# Main.net
KiCad netlist of a schematic drawn in Altium Designer
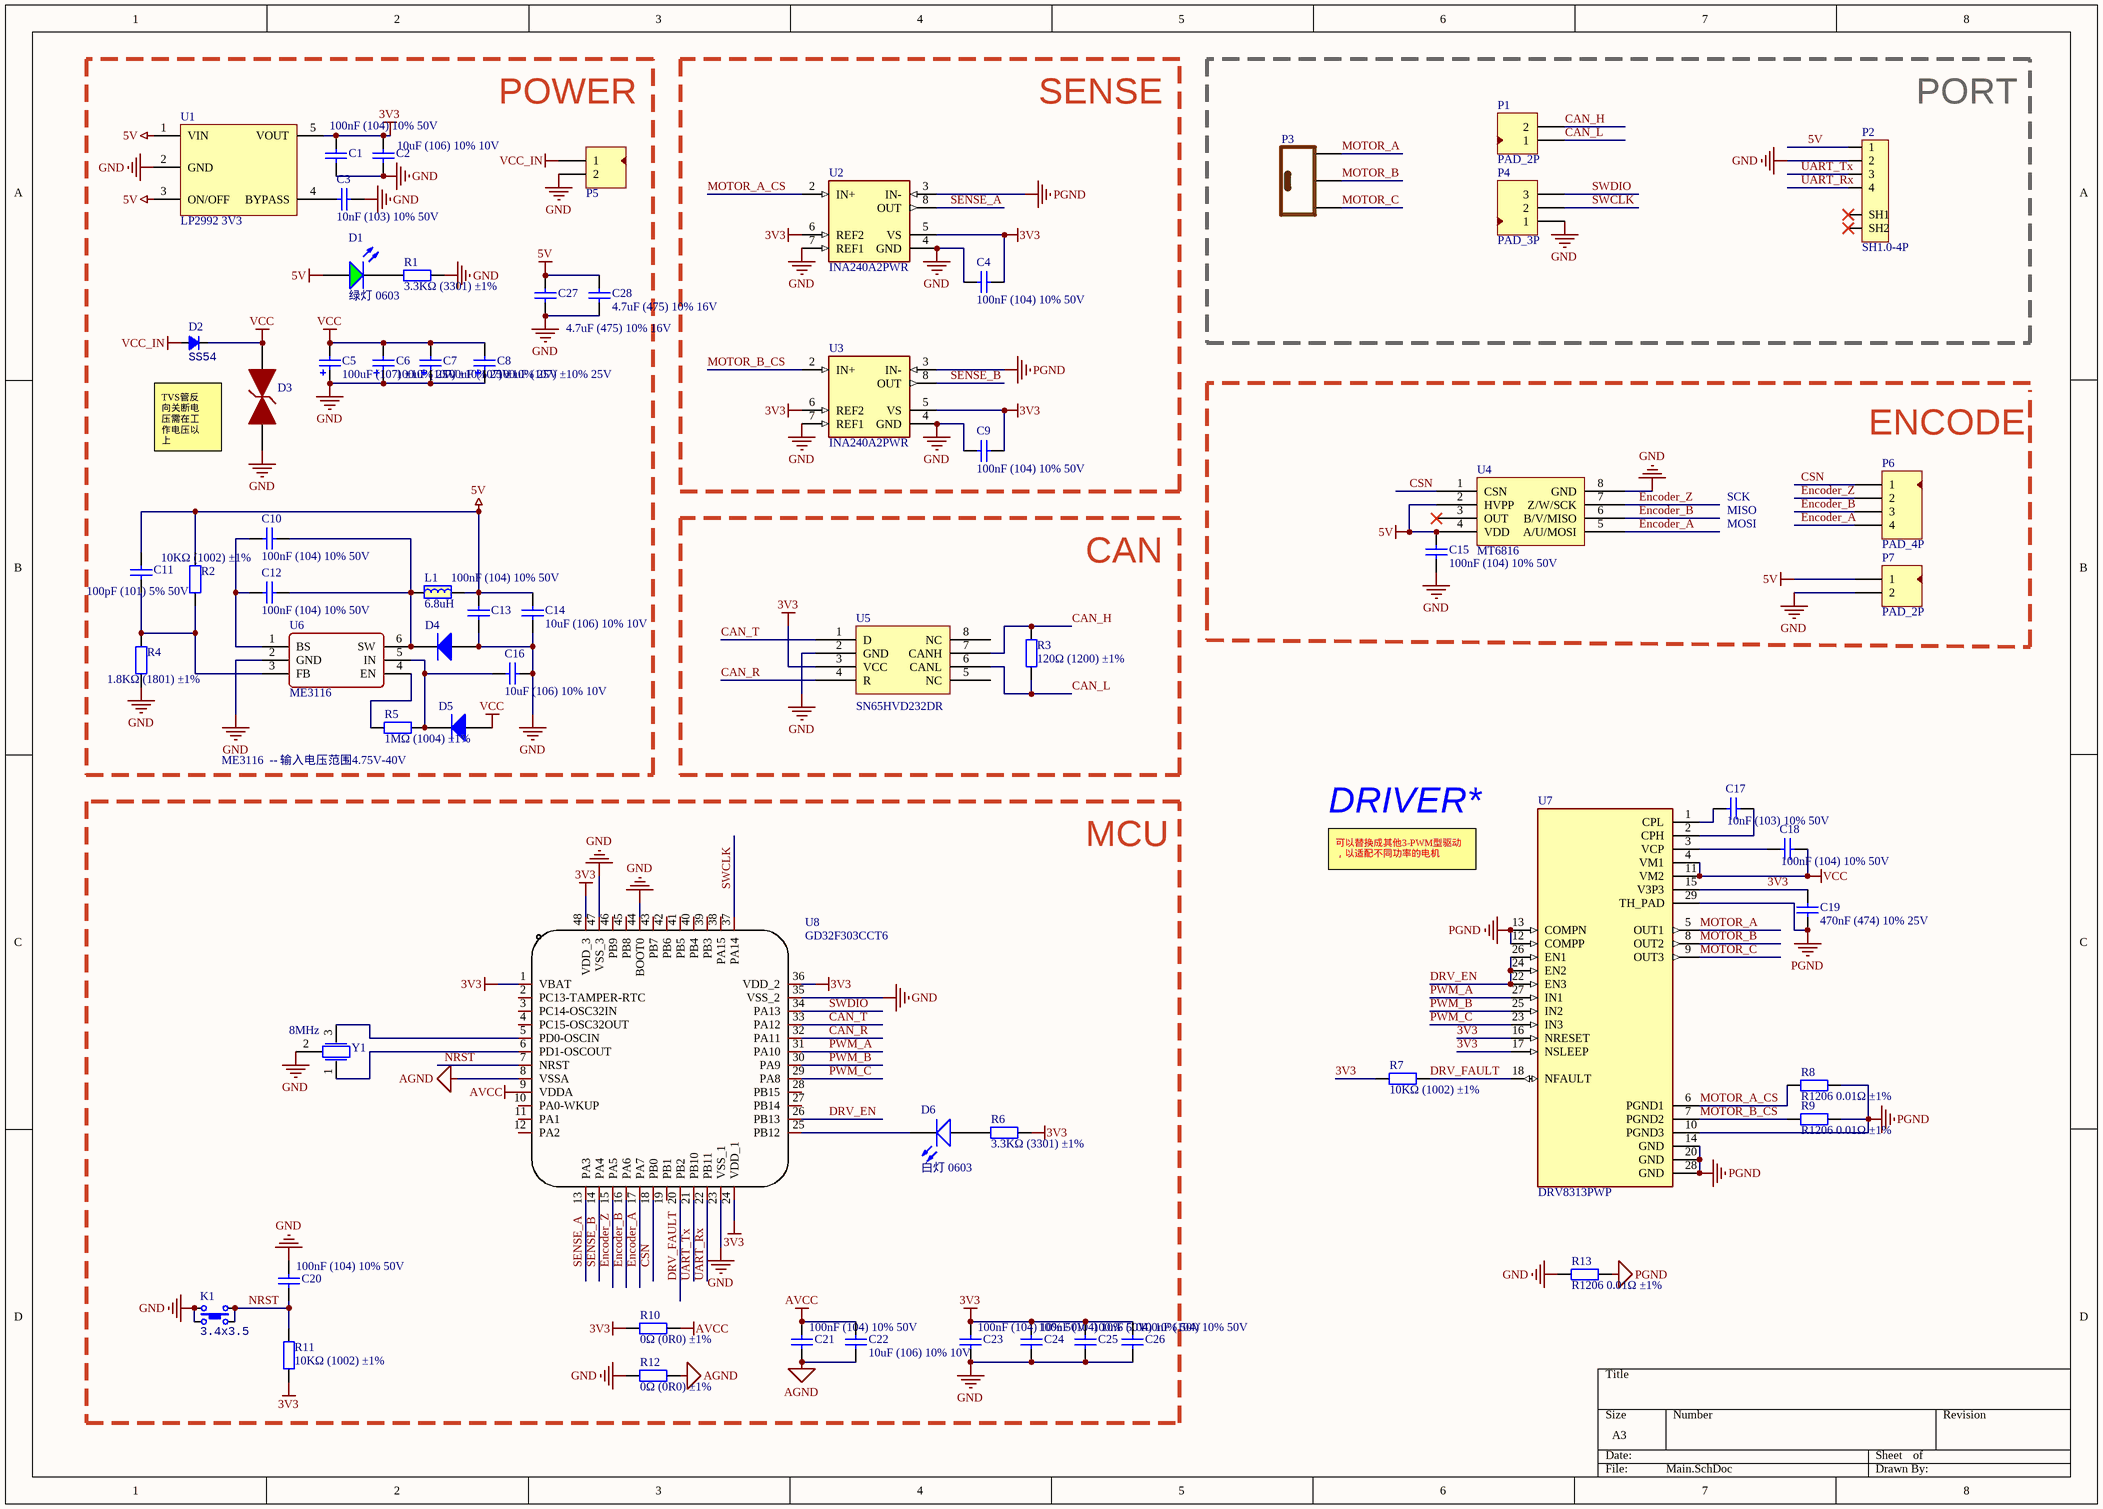
[diagram p0: Main.SchDoc]

(export (version "E")
  (design (tool "Eeschema 10.0.6"))
  (components
    (comp (ref "C1")
      (value "100nF (104) 10% 50V")
      (footprint "0603_C")
      (description "贴片电容")
      (libsource (lib "My_Integrated_Library") (part "0603 100nF (104) 10% 50V"))
    )
    (comp (ref "C2")
      (value "10uF (106) 10% 10V")
      (footprint "0603_C")
      (description "贴片电容")
      (libsource (lib "My_Integrated_Library") (part "0603 10uF (106) 10% 10V"))
    )
    (comp (ref "C3")
      (value "10nF (103) 10% 50V")
      (footprint "0603_C")
      (description "贴片电容")
      (libsource (lib "My_Integrated_Library") (part "0603 10nF (103) 10% 50V"))
    )
    (comp (ref "C4")
      (value "100nF (104) 10% 50V")
      (footprint "0603_C")
      (description "贴片电容")
      (libsource (lib "My_Integrated_Library") (part "0603 100nF (104) 10% 50V"))
    )
    (comp (ref "C5")
      (value "100uF (107) ±10% 25V")
      (footprint "CASE-B_3528")
      (description "钽电容")
      (libsource (lib "My_Integrated_Library") (part "3528 100uF (107) 10% 25V"))
    )
    (comp (ref "C6")
      (value "100uF (107) ±10% 25V")
      (footprint "CASE-B_3528")
      (description "钽电容")
      (libsource (lib "My_Integrated_Library") (part "3528 100uF (107) 10% 25V"))
    )
    (comp (ref "C7")
      (value "100uF (107) ±10% 25V")
      (footprint "CASE-B_3528")
      (description "钽电容")
      (libsource (lib "My_Integrated_Library") (part "3528 100uF (107) 10% 25V"))
    )
    (comp (ref "C8")
      (value "100uF (107) ±10% 25V")
      (footprint "CASE-B_3528")
      (description "钽电容")
      (libsource (lib "My_Integrated_Library") (part "3528 100uF (107) 10% 25V"))
    )
    (comp (ref "C9")
      (value "100nF (104) 10% 50V")
      (footprint "0603_C")
      (description "贴片电容")
      (libsource (lib "My_Integrated_Library") (part "0603 100nF (104) 10% 50V"))
    )
    (comp (ref "C10")
      (value "100nF (104) 10% 50V")
      (footprint "0603_C")
      (description "贴片电容")
      (libsource (lib "My_Integrated_Library") (part "0603 100nF (104) 10% 50V"))
    )
    (comp (ref "C11")
      (value "100pF (101) 5% 50V")
      (footprint "0603_C")
      (description "贴片电容")
      (libsource (lib "My_Integrated_Library") (part "0603 100pF (101) 5% 50V"))
    )
    (comp (ref "C12")
      (value "100nF (104) 10% 50V")
      (footprint "0603_C")
      (description "贴片电容")
      (libsource (lib "My_Integrated_Library") (part "0603 100nF (104) 10% 50V"))
    )
    (comp (ref "C13")
      (value "100nF (104) 10% 50V")
      (footprint "0603_C")
      (description "贴片电容")
      (libsource (lib "My_Integrated_Library") (part "0603 100nF (104) 10% 50V"))
    )
    (comp (ref "C14")
      (value "10uF (106) 10% 10V")
      (footprint "0603_C")
      (description "贴片电容")
      (libsource (lib "My_Integrated_Library") (part "0603 10uF (106) 10% 10V"))
    )
    (comp (ref "C15")
      (value "100nF (104) 10% 50V")
      (footprint "0603_C")
      (description "贴片电容")
      (libsource (lib "My_Integrated_Library") (part "0603 100nF (104) 10% 50V"))
    )
    (comp (ref "C16")
      (value "10uF (106) 10% 10V")
      (footprint "0603_C")
      (description "贴片电容")
      (libsource (lib "My_Integrated_Library") (part "0603 10uF (106) 10% 10V"))
    )
    (comp (ref "C17")
      (value "10nF (103) 10% 50V")
      (footprint "0603_C")
      (description "贴片电容")
      (libsource (lib "My_Integrated_Library") (part "0603 10nF (103) 10% 50V"))
    )
    (comp (ref "C18")
      (value "100nF (104) 10% 50V")
      (footprint "0603_C")
      (description "贴片电容")
      (libsource (lib "My_Integrated_Library") (part "0603 100nF (104) 10% 50V"))
    )
    (comp (ref "C19")
      (value "470nF (474) 10% 25V")
      (footprint "0603_C")
      (description "贴片电容")
      (libsource (lib "My_Integrated_Library") (part "0603 470nF (474) 10% 25V"))
    )
    (comp (ref "C20")
      (value "100nF (104) 10% 50V")
      (footprint "0603_C")
      (description "贴片电容")
      (libsource (lib "My_Integrated_Library") (part "0603 100nF (104) 10% 50V"))
    )
    (comp (ref "C21")
      (value "100nF (104) 10% 50V")
      (footprint "0603_C")
      (description "贴片电容")
      (libsource (lib "My_Integrated_Library") (part "0603 100nF (104) 10% 50V"))
    )
    (comp (ref "C22")
      (value "10uF (106) 10% 10V")
      (footprint "0603_C")
      (description "贴片电容")
      (libsource (lib "My_Integrated_Library") (part "0603 10uF (106) 10% 10V"))
    )
    (comp (ref "C23")
      (value "100nF (104) 10% 50V")
      (footprint "0603_C")
      (description "贴片电容")
      (libsource (lib "My_Integrated_Library") (part "0603 100nF (104) 10% 50V"))
    )
    (comp (ref "C24")
      (value "100nF (104) 10% 50V")
      (footprint "0603_C")
      (description "贴片电容")
      (libsource (lib "My_Integrated_Library") (part "0603 100nF (104) 10% 50V"))
    )
    (comp (ref "C25")
      (value "100nF (104) 10% 50V")
      (footprint "0603_C")
      (description "贴片电容")
      (libsource (lib "My_Integrated_Library") (part "0603 100nF (104) 10% 50V"))
    )
    (comp (ref "C26")
      (value "100nF (104) 10% 50V")
      (footprint "0603_C")
      (description "贴片电容")
      (libsource (lib "My_Integrated_Library") (part "0603 100nF (104) 10% 50V"))
    )
    (comp (ref "C27")
      (value "4.7uF (475) 10% 16V")
      (footprint "0603_C")
      (description "贴片电容")
      (libsource (lib "My_Integrated_Library") (part "0603 4.7uF (475) 10% 16V"))
    )
    (comp (ref "C28")
      (value "4.7uF (475) 10% 16V")
      (footprint "0603_C")
      (description "贴片电容")
      (libsource (lib "My_Integrated_Library") (part "0603 4.7uF (475) 10% 16V"))
    )
    (comp (ref "D1")
      (value "绿灯 0603")
      (footprint "0603_LED_S1")
      (description "发光二极管")
      (libsource (lib "My_Integrated_Library") (part "0603 绿灯"))
    )
    (comp (ref "D2")
      (value "SS54")
      (footprint "DO-214AC")
      (description "Diode")
      (libsource (lib "KitSprout") (part "Diode_SMA"))
    )
    (comp (ref "D3")
      (value "SMBJ28CA")
      (footprint "SMBJ-CA_MFG")
      (libsource (lib "MyPcbLib") (part "SMBJ28CA"))
    )
    (comp (ref "D4")
      (value "二极管-5B5819WS")
      (footprint "SOD-323")
      (description "40V")
      (libsource (lib "MyPcbLib") (part "二极管-5B5817WS"))
    )
    (comp (ref "D5")
      (value "二极管-5B5819WS")
      (footprint "SOD-323")
      (description "40V")
      (libsource (lib "MyPcbLib") (part "二极管-5B5817WS"))
    )
    (comp (ref "D6")
      (value "白灯 0603")
      (footprint "0603_LED_S1")
      (description "发光二极管")
      (libsource (lib "My_Integrated_Library") (part "0603 白灯"))
    )
    (comp (ref "K1")
      (value "3.4x3.5")
      (footprint "ButtonTACT_3.5*3.55_90")
      (description "Button")
      (fields (field (name "Comment") "TACT 4P"))
      (libsource (lib "KitSprout") (part "ButtonTACT"))
    )
    (comp (ref "L1") (value "6.8uH") (footprint "IND-201612") (libsource (lib "MyPcbLib") (part "电感-201612")))
    (comp (ref "P1")
      (value "PAD_2P")
      (footprint "接线焊接点_2P")
      (description "导线焊接点")
      (libsource (lib "") (part "PAD_2P_1"))
    )
    (comp (ref "P2")
      (value "SH1.0-4P")
      (footprint "XP4")
      (libsource (lib "My_Integrated_Library") (part "SH1.0-4P"))
    )
    (comp (ref "P3")
      (value "电机接插件-3P")
      (footprint "AMASS-MR30-M")
      (description "AMASS MR30")
      (libsource (lib "MyPcbLib") (part "电机接插件-3P"))
    )
    (comp (ref "P4")
      (value "PAD_3P")
      (footprint "接线焊接点_3P")
      (description "导线焊接点")
      (libsource (lib "My_Integrated_Library") (part "PAD_3P"))
    )
    (comp (ref "P5")
      (value "Header 2")
      (footprint "HDR1X2")
      (description "接插件")
      (fields (field (name "PUBLISHER") "Altium Limited"))
      (libsource (lib "My_Integrated_Library") (part "Header 2"))
    )
    (comp (ref "P6")
      (value "PAD_4P")
      (footprint "接线焊接点_4P")
      (description "导线焊接点")
      (libsource (lib "My_Integrated_Library") (part "PAD_4P"))
    )
    (comp (ref "P7")
      (value "PAD_2P")
      (footprint "接线焊接点_2P")
      (description "导线焊接点")
      (libsource (lib "My_Integrated_Library") (part "PAD_2P"))
    )
    (comp (ref "R1")
      (value "3.3KΩ (3301) ±1%")
      (footprint "0603_R")
      (description "贴片电阻")
      (libsource (lib "My_Integrated_Library") (part "0603 3.3KΩ (3301) 1%"))
    )
    (comp (ref "R2")
      (value "10KΩ (1002) ±1%")
      (footprint "0603_R")
      (description "贴片电阻")
      (libsource (lib "") (part "0603 10KΩ (1002) 1%_1"))
    )
    (comp (ref "R3")
      (value "120Ω (1200) ±1%")
      (footprint "0603_R")
      (description "贴片电阻")
      (libsource (lib "My_Integrated_Library") (part "0603 120Ω (1200) 1%"))
    )
    (comp (ref "R4")
      (value "1.8KΩ (1801) ±1%")
      (footprint "0603_R")
      (description "贴片电阻")
      (libsource (lib "My_Integrated_Library") (part "0603 1.8KΩ (1801) 1%"))
    )
    (comp (ref "R5")
      (value "1MΩ (1004) ±1%")
      (footprint "0603_R")
      (description "贴片电阻")
      (libsource (lib "My_Integrated_Library") (part "0603 1MΩ (1004) 1%"))
    )
    (comp (ref "R6")
      (value "3.3KΩ (3301) ±1%")
      (footprint "0603_R")
      (description "贴片电阻")
      (libsource (lib "My_Integrated_Library") (part "0603 3.3KΩ (3301) 1%"))
    )
    (comp (ref "R7")
      (value "10KΩ (1002) ±1%")
      (footprint "0603_R")
      (description "贴片电阻")
      (libsource (lib "My_Integrated_Library") (part "0603 10KΩ (1002) 1%"))
    )
    (comp (ref "R8")
      (value "R1206 0.01Ω ±1%")
      (footprint "1206_R")
      (description "电流检测电阻")
      (libsource (lib "My_Integrated_Library") (part "1206 0.005Ω 1%"))
    )
    (comp (ref "R9")
      (value "R1206 0.01Ω ±1%")
      (footprint "1206_R")
      (description "电流检测电阻")
      (libsource (lib "My_Integrated_Library") (part "1206 0.005Ω 1%"))
    )
    (comp (ref "R10")
      (value "0Ω (0R0) ±1%")
      (footprint "0603_R")
      (description "贴片电阻")
      (libsource (lib "My_Integrated_Library") (part "0603 0Ω (0R0) 1%"))
    )
    (comp (ref "R11")
      (value "10KΩ (1002) ±1%")
      (footprint "0603_R")
      (description "贴片电阻")
      (libsource (lib "") (part "0603 10KΩ (1002) 1%_1"))
    )
    (comp (ref "R12")
      (value "0Ω (0R0) ±1%")
      (footprint "0603_R")
      (description "贴片电阻")
      (libsource (lib "My_Integrated_Library") (part "0603 0Ω (0R0) 1%"))
    )
    (comp (ref "R13")
      (value "R1206 0.01Ω ±1%")
      (footprint "1206_R")
      (description "电流检测电阻")
      (libsource (lib "My_Integrated_Library") (part "1206 0.005Ω 1%"))
    )
    (comp (ref "U1")
      (value "LP2992 3V3")
      (footprint "SOT23-5")
      (description "LDO")
      (libsource (lib "MyPcbLib") (part "LP2992"))
    )
    (comp (ref "U2")
      (value "INA240A2PWR")
      (footprint "SOP65 P640X120-8N")
      (fields (field (name "MF") "Texas Instruments"))
      (libsource (lib "mLib") (part "INA240A2PWR"))
    )
    (comp (ref "U3")
      (value "INA240A2PWR")
      (footprint "SOP65 P640X120-8N")
      (fields (field (name "MF") "Texas Instruments"))
      (libsource (lib "mLib") (part "INA240A2PWR"))
    )
    (comp (ref "U4")
      (value "MT6816")
      (footprint "SOP8-PP-AT8870")
      (libsource (lib "My_Integrated_Library") (part "MT6816"))
    )
    (comp (ref "U5")
      (value "SN65HVD232D")
      (footprint "SO-8")
      (fields
        (field (name "MANUFACTURER") "Texas Instruments")
        (field (name "MANUFACTURER PART NUMBER") "SN65HVD232DR")
      )
      (libsource (lib "MyPcbLib") (part "SN65HVD232D"))
    )
    (comp (ref "U6")
      (value "ME3116")
      (footprint "SOT23-6")
      (description "DC-DC")
      (libsource (lib "MyPcbLib") (part "ME3116"))
    )
    (comp (ref "U7")
      (value "DRV8313PWP")
      (footprint "HTSSOP-28")
      (description "65-V max, 3-A peak 3-phase motor driver 28-HTSSOP -40 to 125")
      (fields (field (name "MF") "Texas Instruments"))
      (libsource (lib "MyPcbLib") (part "DRV8313PWP"))
    )
    (comp (ref "U8")
      (value "GD32F303CCT6")
      (footprint "LQFP_48")
      (libsource (lib "MCU") (part "GD32F303CCT6"))
    )
    (comp (ref "Y1")
      (value "8MHz")
      (footprint "晶振-3P")
      (description "村田贴片")
      (libsource (lib "MyPcbLib") (part "晶振-3Pin"))
    )
  )
  (nets
    (net (code "1") (name "/CAN_H") (class "Default")
      (node (ref "P1") (pin "2") (pinfunction "2_2") (pintype "passive"))
      (node (ref "R3") (pin "2") (pinfunction "2_2") (pintype "passive"))
      (node (ref "U5") (pin "7") (pinfunction "CANH_7") (pintype "passive"))
    )
    (net (code "2") (name "/CAN_L") (class "Default")
      (node (ref "P1") (pin "1") (pinfunction "1_1") (pintype "passive"))
      (node (ref "R3") (pin "1") (pinfunction "1_1") (pintype "passive"))
      (node (ref "U5") (pin "6") (pinfunction "CANL_6") (pintype "passive"))
    )
    (net (code "3") (name "/CAN_R") (class "Default")
      (node (ref "U5") (pin "4") (pinfunction "R_4") (pintype "passive"))
      (node (ref "U8") (pin "32") (pinfunction "PA11_32") (pintype "passive"))
    )
    (net (code "4") (name "/CAN_T") (class "Default")
      (node (ref "U5") (pin "1") (pinfunction "D_1") (pintype "passive"))
      (node (ref "U8") (pin "33") (pinfunction "PA12_33") (pintype "passive"))
    )
    (net (code "5") (name "/CSN") (class "Default")
      (node (ref "P6") (pin "1") (pinfunction "1_1") (pintype "passive"))
      (node (ref "U4") (pin "1") (pinfunction "CSN_1") (pintype "passive"))
      (node (ref "U8") (pin "18") (pinfunction "PB0_18") (pintype "passive"))
    )
    (net (code "6") (name "/DRV_EN") (class "Default")
      (node (ref "U7") (pin "22") (pinfunction "EN3_22") (pintype "input"))
      (node (ref "U7") (pin "24") (pinfunction "EN2_24") (pintype "input"))
      (node (ref "U7") (pin "26") (pinfunction "EN1_26") (pintype "input"))
      (node (ref "U8") (pin "26") (pinfunction "PB13_26") (pintype "passive"))
    )
    (net (code "7") (name "/DRV_FAULT") (class "Default")
      (node (ref "R7") (pin "2") (pinfunction "2_2") (pintype "passive"))
      (node (ref "U7") (pin "18") (pinfunction "NFAULT_18") (pintype "bidirectional"))
      (node (ref "U8") (pin "20") (pinfunction "PB2_20") (pintype "passive"))
    )
    (net (code "8") (name "/Encoder_A") (class "Default")
      (node (ref "P6") (pin "4") (pinfunction "4_4") (pintype "passive"))
      (node (ref "U4") (pin "5") (pinfunction "A/U/MOSI_5") (pintype "passive"))
      (node (ref "U8") (pin "17") (pinfunction "PA7_17") (pintype "passive"))
    )
    (net (code "9") (name "/Encoder_B") (class "Default")
      (node (ref "P6") (pin "3") (pinfunction "3_3") (pintype "passive"))
      (node (ref "U4") (pin "6") (pinfunction "B/V/MISO_6") (pintype "passive"))
      (node (ref "U8") (pin "16") (pinfunction "PA6_16") (pintype "passive"))
    )
    (net (code "10") (name "/Encoder_Z") (class "Default")
      (node (ref "P6") (pin "2") (pinfunction "2_2") (pintype "passive"))
      (node (ref "U4") (pin "7") (pinfunction "Z/W/SCK_7") (pintype "passive"))
      (node (ref "U8") (pin "15") (pinfunction "PA5_15") (pintype "passive"))
    )
    (net (code "11") (name "/MOTOR_A") (class "Default")
      (node (ref "P3") (pin "3") (pinfunction "3_3") (pintype "passive"))
      (node (ref "U7") (pin "5") (pinfunction "OUT1_5") (pintype "output"))
    )
    (net (code "12") (name "/MOTOR_A_CS") (class "Default")
      (node (ref "R8") (pin "1") (pinfunction "1_1") (pintype "passive"))
      (node (ref "U2") (pin "2") (pinfunction "IN+_2") (pintype "input"))
      (node (ref "U7") (pin "6") (pinfunction "PGND1_6") (pintype "power_in"))
    )
    (net (code "13") (name "/MOTOR_B") (class "Default")
      (node (ref "P3") (pin "2") (pinfunction "2_2") (pintype "passive"))
      (node (ref "U7") (pin "8") (pinfunction "OUT2_8") (pintype "output"))
    )
    (net (code "14") (name "/MOTOR_B_CS") (class "Default")
      (node (ref "R9") (pin "1") (pinfunction "1_1") (pintype "passive"))
      (node (ref "U3") (pin "2") (pinfunction "IN+_2") (pintype "input"))
      (node (ref "U7") (pin "7") (pinfunction "PGND2_7") (pintype "power_in"))
    )
    (net (code "15") (name "/MOTOR_C") (class "Default")
      (node (ref "P3") (pin "1") (pinfunction "1_1") (pintype "passive"))
      (node (ref "U7") (pin "9") (pinfunction "OUT3_9") (pintype "output"))
    )
    (net (code "16") (name "/NRST") (class "Default")
      (node (ref "C20") (pin "1") (pinfunction "1_1") (pintype "passive"))
      (node (ref "K1") (pin "1") (pinfunction "1_1") (pintype "passive"))
      (node (ref "K1") (pin "3") (pinfunction "3_3") (pintype "passive"))
      (node (ref "R11") (pin "2") (pinfunction "2_2") (pintype "passive"))
      (node (ref "U8") (pin "7") (pinfunction "NRST_7") (pintype "passive"))
    )
    (net (code "17") (name "/PWM_A") (class "Default")
      (node (ref "U7") (pin "27") (pinfunction "IN1_27") (pintype "input"))
      (node (ref "U8") (pin "31") (pinfunction "PA10_31") (pintype "passive"))
    )
    (net (code "18") (name "/PWM_B") (class "Default")
      (node (ref "U7") (pin "25") (pinfunction "IN2_25") (pintype "input"))
      (node (ref "U8") (pin "30") (pinfunction "PA9_30") (pintype "passive"))
    )
    (net (code "19") (name "/PWM_C") (class "Default")
      (node (ref "U7") (pin "23") (pinfunction "IN3_23") (pintype "input"))
      (node (ref "U8") (pin "29") (pinfunction "PA8_29") (pintype "passive"))
    )
    (net (code "20") (name "/SENSE_A") (class "Default")
      (node (ref "U2") (pin "8") (pinfunction "OUT_8") (pintype "output"))
      (node (ref "U8") (pin "13") (pinfunction "PA3_13") (pintype "passive"))
    )
    (net (code "21") (name "/SENSE_B") (class "Default")
      (node (ref "U3") (pin "8") (pinfunction "OUT_8") (pintype "output"))
      (node (ref "U8") (pin "14") (pinfunction "PA4_14") (pintype "passive"))
    )
    (net (code "22") (name "/SWCLK") (class "Default")
      (node (ref "P4") (pin "2") (pinfunction "2_2") (pintype "passive"))
      (node (ref "U8") (pin "37") (pinfunction "PA14_37") (pintype "passive"))
    )
    (net (code "23") (name "/SWDIO") (class "Default")
      (node (ref "P4") (pin "3") (pinfunction "3_3") (pintype "passive"))
      (node (ref "U8") (pin "34") (pinfunction "PA13_34") (pintype "passive"))
    )
    (net (code "24") (name "/UART_Rx") (class "Default")
      (node (ref "P2") (pin "4") (pinfunction "4_4") (pintype "passive"))
      (node (ref "U8") (pin "22") (pinfunction "PB11_22") (pintype "passive"))
    )
    (net (code "25") (name "/UART_Tx") (class "Default")
      (node (ref "P2") (pin "3") (pinfunction "3_3") (pintype "passive"))
      (node (ref "U8") (pin "21") (pinfunction "PB10_21") (pintype "passive"))
    )
    (net (code "26") (name "3V3") (class "Default")
      (node (ref "C1") (pin "2") (pinfunction "2_2") (pintype "passive"))
      (node (ref "C19") (pin "2") (pinfunction "2_2") (pintype "passive"))
      (node (ref "C2") (pin "2") (pinfunction "2_2") (pintype "passive"))
      (node (ref "C23") (pin "2") (pinfunction "2_2") (pintype "passive"))
      (node (ref "C24") (pin "2") (pinfunction "2_2") (pintype "passive"))
      (node (ref "C25") (pin "2") (pinfunction "2_2") (pintype "passive"))
      (node (ref "C26") (pin "2") (pinfunction "2_2") (pintype "passive"))
      (node (ref "C4") (pin "2") (pinfunction "2_2") (pintype "passive"))
      (node (ref "C9") (pin "1") (pinfunction "1_1") (pintype "passive"))
      (node (ref "R10") (pin "1") (pinfunction "1_1") (pintype "passive"))
      (node (ref "R11") (pin "1") (pinfunction "1_1") (pintype "passive"))
      (node (ref "R6") (pin "2") (pinfunction "2_2") (pintype "passive"))
      (node (ref "R7") (pin "1") (pinfunction "1_1") (pintype "passive"))
      (node (ref "U1") (pin "5") (pinfunction "VOUT_5") (pintype "passive"))
      (node (ref "U2") (pin "5") (pinfunction "VS_5") (pintype "power_in"))
      (node (ref "U2") (pin "6") (pinfunction "REF2_6") (pintype "input"))
      (node (ref "U3") (pin "5") (pinfunction "VS_5") (pintype "power_in"))
      (node (ref "U3") (pin "6") (pinfunction "REF2_6") (pintype "input"))
      (node (ref "U5") (pin "3") (pinfunction "VCC_3") (pintype "passive"))
      (node (ref "U7") (pin "15") (pinfunction "V3P3_15") (pintype "power_in"))
      (node (ref "U7") (pin "16") (pinfunction "NRESET_16") (pintype "input"))
      (node (ref "U7") (pin "17") (pinfunction "NSLEEP_17") (pintype "input"))
      (node (ref "U8") (pin "1") (pinfunction "VBAT_1") (pintype "passive"))
      (node (ref "U8") (pin "24") (pinfunction "VDD_1_24") (pintype "passive"))
      (node (ref "U8") (pin "36") (pinfunction "VDD_2_36") (pintype "passive"))
      (node (ref "U8") (pin "48") (pinfunction "VDD_3_48") (pintype "passive"))
    )
    (net (code "27") (name "5V") (class "Default")
      (node (ref "C11") (pin "2") (pinfunction "2_2") (pintype "passive"))
      (node (ref "C13") (pin "2") (pinfunction "2_2") (pintype "passive"))
      (node (ref "C14") (pin "2") (pinfunction "2_2") (pintype "passive"))
      (node (ref "C15") (pin "2") (pinfunction "2_2") (pintype "passive"))
      (node (ref "C27") (pin "2") (pinfunction "2_2") (pintype "passive"))
      (node (ref "C28") (pin "2") (pinfunction "2_2") (pintype "passive"))
      (node (ref "D1") (pin "A") (pinfunction "A_A") (pintype "passive"))
      (node (ref "L1") (pin "2") (pinfunction "2_2") (pintype "passive"))
      (node (ref "P2") (pin "1") (pinfunction "1_1") (pintype "passive"))
      (node (ref "P7") (pin "1") (pinfunction "1_1") (pintype "passive"))
      (node (ref "R2") (pin "2") (pinfunction "2_2") (pintype "passive"))
      (node (ref "U1") (pin "1") (pinfunction "VIN_1") (pintype "passive"))
      (node (ref "U1") (pin "3") (pinfunction "ON/OFF_3") (pintype "passive"))
      (node (ref "U4") (pin "2") (pinfunction "HVPP_2") (pintype "passive"))
      (node (ref "U4") (pin "4") (pinfunction "VDD_4") (pintype "passive"))
    )
    (net (code "28") (name "AGND") (class "Default")
      (node (ref "C21") (pin "1") (pinfunction "1_1") (pintype "passive"))
      (node (ref "C22") (pin "1") (pinfunction "1_1") (pintype "passive"))
      (node (ref "R12") (pin "2") (pinfunction "2_2") (pintype "passive"))
      (node (ref "U8") (pin "8") (pinfunction "VSSA_8") (pintype "passive"))
    )
    (net (code "29") (name "AVCC") (class "Default")
      (node (ref "C21") (pin "2") (pinfunction "2_2") (pintype "passive"))
      (node (ref "C22") (pin "2") (pinfunction "2_2") (pintype "passive"))
      (node (ref "R10") (pin "2") (pinfunction "2_2") (pintype "passive"))
      (node (ref "U8") (pin "9") (pinfunction "VDDA_9") (pintype "passive"))
    )
    (net (code "30") (name "GND") (class "Default")
      (node (ref "C1") (pin "1") (pinfunction "1_1") (pintype "passive"))
      (node (ref "C13") (pin "1") (pinfunction "1_1") (pintype "passive"))
      (node (ref "C14") (pin "1") (pinfunction "1_1") (pintype "passive"))
      (node (ref "C15") (pin "1") (pinfunction "1_1") (pintype "passive"))
      (node (ref "C16") (pin "1") (pinfunction "1_1") (pintype "passive"))
      (node (ref "C2") (pin "1") (pinfunction "1_1") (pintype "passive"))
      (node (ref "C20") (pin "2") (pinfunction "2_2") (pintype "passive"))
      (node (ref "C23") (pin "1") (pinfunction "1_1") (pintype "passive"))
      (node (ref "C24") (pin "1") (pinfunction "1_1") (pintype "passive"))
      (node (ref "C25") (pin "1") (pinfunction "1_1") (pintype "passive"))
      (node (ref "C26") (pin "1") (pinfunction "1_1") (pintype "passive"))
      (node (ref "C27") (pin "1") (pinfunction "1_1") (pintype "passive"))
      (node (ref "C28") (pin "1") (pinfunction "1_1") (pintype "passive"))
      (node (ref "C3") (pin "2") (pinfunction "2_2") (pintype "passive"))
      (node (ref "C4") (pin "1") (pinfunction "1_1") (pintype "passive"))
      (node (ref "C5") (pin "1") (pinfunction "1_1") (pintype "passive"))
      (node (ref "C6") (pin "1") (pinfunction "1_1") (pintype "passive"))
      (node (ref "C7") (pin "1") (pinfunction "1_1") (pintype "passive"))
      (node (ref "C8") (pin "1") (pinfunction "1_1") (pintype "passive"))
      (node (ref "C9") (pin "2") (pinfunction "2_2") (pintype "passive"))
      (node (ref "D3") (pin "1") (pinfunction "1_1") (pintype "passive"))
      (node (ref "D4") (pin "1") (pinfunction "A_1") (pintype "passive"))
      (node (ref "K1") (pin "2") (pinfunction "2_2") (pintype "passive"))
      (node (ref "K1") (pin "4") (pinfunction "4_4") (pintype "passive"))
      (node (ref "P2") (pin "2") (pinfunction "2_2") (pintype "passive"))
      (node (ref "P4") (pin "1") (pinfunction "1_1") (pintype "passive"))
      (node (ref "P5") (pin "2") (pinfunction "2_2") (pintype "passive"))
      (node (ref "P7") (pin "2") (pinfunction "2_2") (pintype "passive"))
      (node (ref "R1") (pin "2") (pinfunction "2_2") (pintype "passive"))
      (node (ref "R12") (pin "1") (pinfunction "1_1") (pintype "passive"))
      (node (ref "R13") (pin "1") (pinfunction "1_1") (pintype "passive"))
      (node (ref "R4") (pin "1") (pinfunction "1_1") (pintype "passive"))
      (node (ref "U1") (pin "2") (pinfunction "GND_2") (pintype "passive"))
      (node (ref "U2") (pin "4") (pinfunction "GND_4") (pintype "power_in"))
      (node (ref "U2") (pin "7") (pinfunction "REF1_7") (pintype "input"))
      (node (ref "U3") (pin "4") (pinfunction "GND_4") (pintype "power_in"))
      (node (ref "U3") (pin "7") (pinfunction "REF1_7") (pintype "input"))
      (node (ref "U4") (pin "8") (pinfunction "GND_8") (pintype "passive"))
      (node (ref "U5") (pin "2") (pinfunction "GND_2") (pintype "passive"))
      (node (ref "U6") (pin "2") (pinfunction "GND_2") (pintype "passive"))
      (node (ref "U8") (pin "23") (pinfunction "VSS_1_23") (pintype "passive"))
      (node (ref "U8") (pin "35") (pinfunction "VSS_2_35") (pintype "passive"))
      (node (ref "U8") (pin "44") (pinfunction "BOOT0_44") (pintype "passive"))
      (node (ref "U8") (pin "47") (pinfunction "VSS_3_47") (pintype "passive"))
      (node (ref "Y1") (pin "2") (pinfunction "2_2") (pintype "passive"))
    )
    (net (code "31") (name "Net-(D1-PadK)") (class "Default")
      (node (ref "D1") (pin "K") (pinfunction "K_K") (pintype "passive"))
      (node (ref "R1") (pin "1") (pinfunction "1_1") (pintype "passive"))
    )
    (net (code "32") (name "Net-(D4-K)") (class "Default")
      (node (ref "C10") (pin "1") (pinfunction "1_1") (pintype "passive"))
      (node (ref "C12") (pin "1") (pinfunction "1_1") (pintype "passive"))
      (node (ref "D4") (pin "2") (pinfunction "K_2") (pintype "passive"))
      (node (ref "L1") (pin "1") (pintype "passive"))
      (node (ref "U6") (pin "6") (pinfunction "SW_6") (pintype "passive"))
    )
    (net (code "33") (name "Net-(D5-K)") (class "Default")
      (node (ref "C16") (pin "2") (pinfunction "2_2") (pintype "passive"))
      (node (ref "D5") (pin "2") (pinfunction "K_2") (pintype "passive"))
      (node (ref "R5") (pin "2") (pinfunction "2_2") (pintype "passive"))
      (node (ref "U6") (pin "5") (pinfunction "IN_5") (pintype "passive"))
    )
    (net (code "34") (name "Net-(D6-PadA)") (class "Default")
      (node (ref "D6") (pin "A") (pinfunction "A_A") (pintype "passive"))
      (node (ref "R6") (pin "1") (pinfunction "1_1") (pintype "passive"))
    )
    (net (code "35") (name "Net-(U1-BYPASS)") (class "Default")
      (node (ref "C3") (pin "1") (pinfunction "1_1") (pintype "passive"))
      (node (ref "U1") (pin "4") (pinfunction "BYPASS_4") (pintype "passive"))
    )
    (net (code "36") (name "Net-(U6-BS)") (class "Default")
      (node (ref "C10") (pin "2") (pinfunction "2_2") (pintype "passive"))
      (node (ref "C12") (pin "2") (pinfunction "2_2") (pintype "passive"))
      (node (ref "U6") (pin "1") (pinfunction "BS_1") (pintype "passive"))
    )
    (net (code "37") (name "Net-(U6-EN)") (class "Default")
      (node (ref "R5") (pin "1") (pinfunction "1_1") (pintype "passive"))
      (node (ref "U6") (pin "4") (pinfunction "EN_4") (pintype "passive"))
    )
    (net (code "38") (name "Net-(U6-FB)") (class "Default")
      (node (ref "C11") (pin "1") (pinfunction "1_1") (pintype "passive"))
      (node (ref "R2") (pin "1") (pinfunction "1_1") (pintype "passive"))
      (node (ref "R4") (pin "2") (pinfunction "2_2") (pintype "passive"))
      (node (ref "U6") (pin "3") (pinfunction "FB_3") (pintype "passive"))
    )
    (net (code "39") (name "Net-(U7-CPH)") (class "Default")
      (node (ref "C17") (pin "2") (pinfunction "2_2") (pintype "passive"))
      (node (ref "U7") (pin "2") (pinfunction "CPH_2") (pintype "power_in"))
    )
    (net (code "40") (name "Net-(U7-CPL)") (class "Default")
      (node (ref "C17") (pin "1") (pinfunction "1_1") (pintype "passive"))
      (node (ref "U7") (pin "1") (pinfunction "CPL_1") (pintype "power_in"))
    )
    (net (code "41") (name "Net-(U7-VCP)") (class "Default")
      (node (ref "C18") (pin "2") (pinfunction "2_2") (pintype "passive"))
      (node (ref "U7") (pin "3") (pinfunction "VCP_3") (pintype "power_in"))
    )
    (net (code "42") (name "Net-(U8-PB12)") (class "Default")
      (node (ref "D6") (pin "K") (pinfunction "K_K") (pintype "passive"))
      (node (ref "U8") (pin "25") (pinfunction "PB12_25") (pintype "passive"))
    )
    (net (code "43") (name "Net-(U8-PD0-OSCIN)") (class "Default")
      (node (ref "U8") (pin "5") (pinfunction "PD0-OSCIN_5") (pintype "passive"))
      (node (ref "Y1") (pin "3") (pinfunction "3_3") (pintype "passive"))
    )
    (net (code "44") (name "Net-(U8-PD1-OSCOUT)") (class "Default")
      (node (ref "U8") (pin "6") (pinfunction "PD1-OSCOUT_6") (pintype "passive"))
      (node (ref "Y1") (pin "1") (pinfunction "1_1") (pintype "passive"))
    )
    (net (code "45") (name "PGND") (class "Default")
      (node (ref "C19") (pin "1") (pinfunction "1_1") (pintype "passive"))
      (node (ref "R13") (pin "2") (pinfunction "2_2") (pintype "passive"))
      (node (ref "R8") (pin "2") (pinfunction "2_2") (pintype "passive"))
      (node (ref "R9") (pin "2") (pinfunction "2_2") (pintype "passive"))
      (node (ref "U2") (pin "3") (pinfunction "IN-_3") (pintype "input"))
      (node (ref "U3") (pin "3") (pinfunction "IN-_3") (pintype "input"))
      (node (ref "U7") (pin "10") (pinfunction "PGND3_10") (pintype "power_in"))
      (node (ref "U7") (pin "12") (pinfunction "COMPP_12") (pintype "input"))
      (node (ref "U7") (pin "13") (pinfunction "COMPN_13") (pintype "input"))
      (node (ref "U7") (pin "14") (pinfunction "GND_14") (pintype "power_in"))
      (node (ref "U7") (pin "20") (pinfunction "GND_20") (pintype "power_in"))
      (node (ref "U7") (pin "28") (pinfunction "GND_28") (pintype "power_in"))
      (node (ref "U7") (pin "29") (pinfunction "TH_PAD_29") (pintype "power_in"))
    )
    (net (code "46") (name "VCC") (class "Default")
      (node (ref "C18") (pin "1") (pinfunction "1_1") (pintype "passive"))
      (node (ref "C5") (pin "2") (pinfunction "2_2") (pintype "passive"))
      (node (ref "C6") (pin "2") (pinfunction "2_2") (pintype "passive"))
      (node (ref "C7") (pin "2") (pinfunction "2_2") (pintype "passive"))
      (node (ref "C8") (pin "2") (pinfunction "2_2") (pintype "passive"))
      (node (ref "D2") (pin "2") (pinfunction "K_2") (pintype "passive"))
      (node (ref "D3") (pin "2") (pinfunction "2_2") (pintype "passive"))
      (node (ref "D5") (pin "1") (pinfunction "A_1") (pintype "passive"))
      (node (ref "U7") (pin "11") (pinfunction "VM2_11") (pintype "power_in"))
      (node (ref "U7") (pin "4") (pinfunction "VM1_4") (pintype "power_in"))
    )
    (net (code "47") (name "VCC_IN") (class "Default")
      (node (ref "D2") (pin "1") (pinfunction "A_1") (pintype "passive"))
      (node (ref "P5") (pin "1") (pinfunction "1_1") (pintype "passive"))
    )
    (net (code "48") (name "unconnected-(P2-PadSH1)") (class "Default")
      (node (ref "P2") (pin "SH1") (pinfunction "SH1_SH1") (pintype "passive+no_connect"))
    )
    (net (code "49") (name "unconnected-(P2-PadSH2)") (class "Default")
      (node (ref "P2") (pin "SH2") (pinfunction "SH2_SH2") (pintype "passive+no_connect"))
    )
    (net (code "50") (name "unconnected-(U4-OUT-Pad3)") (class "Default")
      (node (ref "U4") (pin "3") (pinfunction "OUT_3") (pintype "passive+no_connect"))
    )
    (net (code "51") (name "unconnected-(U5-NC-Pad5)") (class "Default")
      (node (ref "U5") (pin "5") (pinfunction "NC_5") (pintype "passive"))
    )
    (net (code "52") (name "unconnected-(U5-NC-Pad8)") (class "Default")
      (node (ref "U5") (pin "8") (pinfunction "NC_8") (pintype "passive"))
    )
    (net (code "53") (name "unconnected-(U8-PA0-WKUP-Pad10)") (class "Default")
      (node (ref "U8") (pin "10") (pinfunction "PA0-WKUP_10") (pintype "passive"))
    )
    (net (code "54") (name "unconnected-(U8-PA1-Pad11)") (class "Default")
      (node (ref "U8") (pin "11") (pinfunction "PA1_11") (pintype "passive"))
    )
    (net (code "55") (name "unconnected-(U8-PA2-Pad12)") (class "Default")
      (node (ref "U8") (pin "12") (pinfunction "PA2_12") (pintype "passive"))
    )
    (net (code "56") (name "unconnected-(U8-PA15-Pad38)") (class "Default")
      (node (ref "U8") (pin "38") (pinfunction "PA15_38") (pintype "passive"))
    )
    (net (code "57") (name "unconnected-(U8-PB1-Pad19)") (class "Default")
      (node (ref "U8") (pin "19") (pinfunction "PB1_19") (pintype "passive"))
    )
    (net (code "58") (name "unconnected-(U8-PB3-Pad39)") (class "Default")
      (node (ref "U8") (pin "39") (pinfunction "PB3_39") (pintype "passive"))
    )
    (net (code "59") (name "unconnected-(U8-PB4-Pad40)") (class "Default")
      (node (ref "U8") (pin "40") (pinfunction "PB4_40") (pintype "passive"))
    )
    (net (code "60") (name "unconnected-(U8-PB5-Pad41)") (class "Default")
      (node (ref "U8") (pin "41") (pinfunction "PB5_41") (pintype "passive"))
    )
    (net (code "61") (name "unconnected-(U8-PB6-Pad42)") (class "Default")
      (node (ref "U8") (pin "42") (pinfunction "PB6_42") (pintype "passive"))
    )
    (net (code "62") (name "unconnected-(U8-PB7-Pad43)") (class "Default")
      (node (ref "U8") (pin "43") (pinfunction "PB7_43") (pintype "passive"))
    )
    (net (code "63") (name "unconnected-(U8-PB8-Pad45)") (class "Default")
      (node (ref "U8") (pin "45") (pinfunction "PB8_45") (pintype "passive"))
    )
    (net (code "64") (name "unconnected-(U8-PB9-Pad46)") (class "Default")
      (node (ref "U8") (pin "46") (pinfunction "PB9_46") (pintype "passive"))
    )
    (net (code "65") (name "unconnected-(U8-PB14-Pad27)") (class "Default")
      (node (ref "U8") (pin "27") (pinfunction "PB14_27") (pintype "passive"))
    )
    (net (code "66") (name "unconnected-(U8-PB15-Pad28)") (class "Default")
      (node (ref "U8") (pin "28") (pinfunction "PB15_28") (pintype "passive"))
    )
    (net (code "67") (name "unconnected-(U8-PC13-TAMPER-RTC-Pad2)") (class "Default")
      (node (ref "U8") (pin "2") (pinfunction "PC13-TAMPER-RTC_2") (pintype "passive"))
    )
    (net (code "68") (name "unconnected-(U8-PC14-OSC32IN-Pad3)") (class "Default")
      (node (ref "U8") (pin "3") (pinfunction "PC14-OSC32IN_3") (pintype "passive"))
    )
    (net (code "69") (name "unconnected-(U8-PC15-OSC32OUT-Pad4)") (class "Default")
      (node (ref "U8") (pin "4") (pinfunction "PC15-OSC32OUT_4") (pintype "passive"))
    )
  )
)
